# basic_tracker.net
KiCad netlist of a schematic drawn in EAGLE
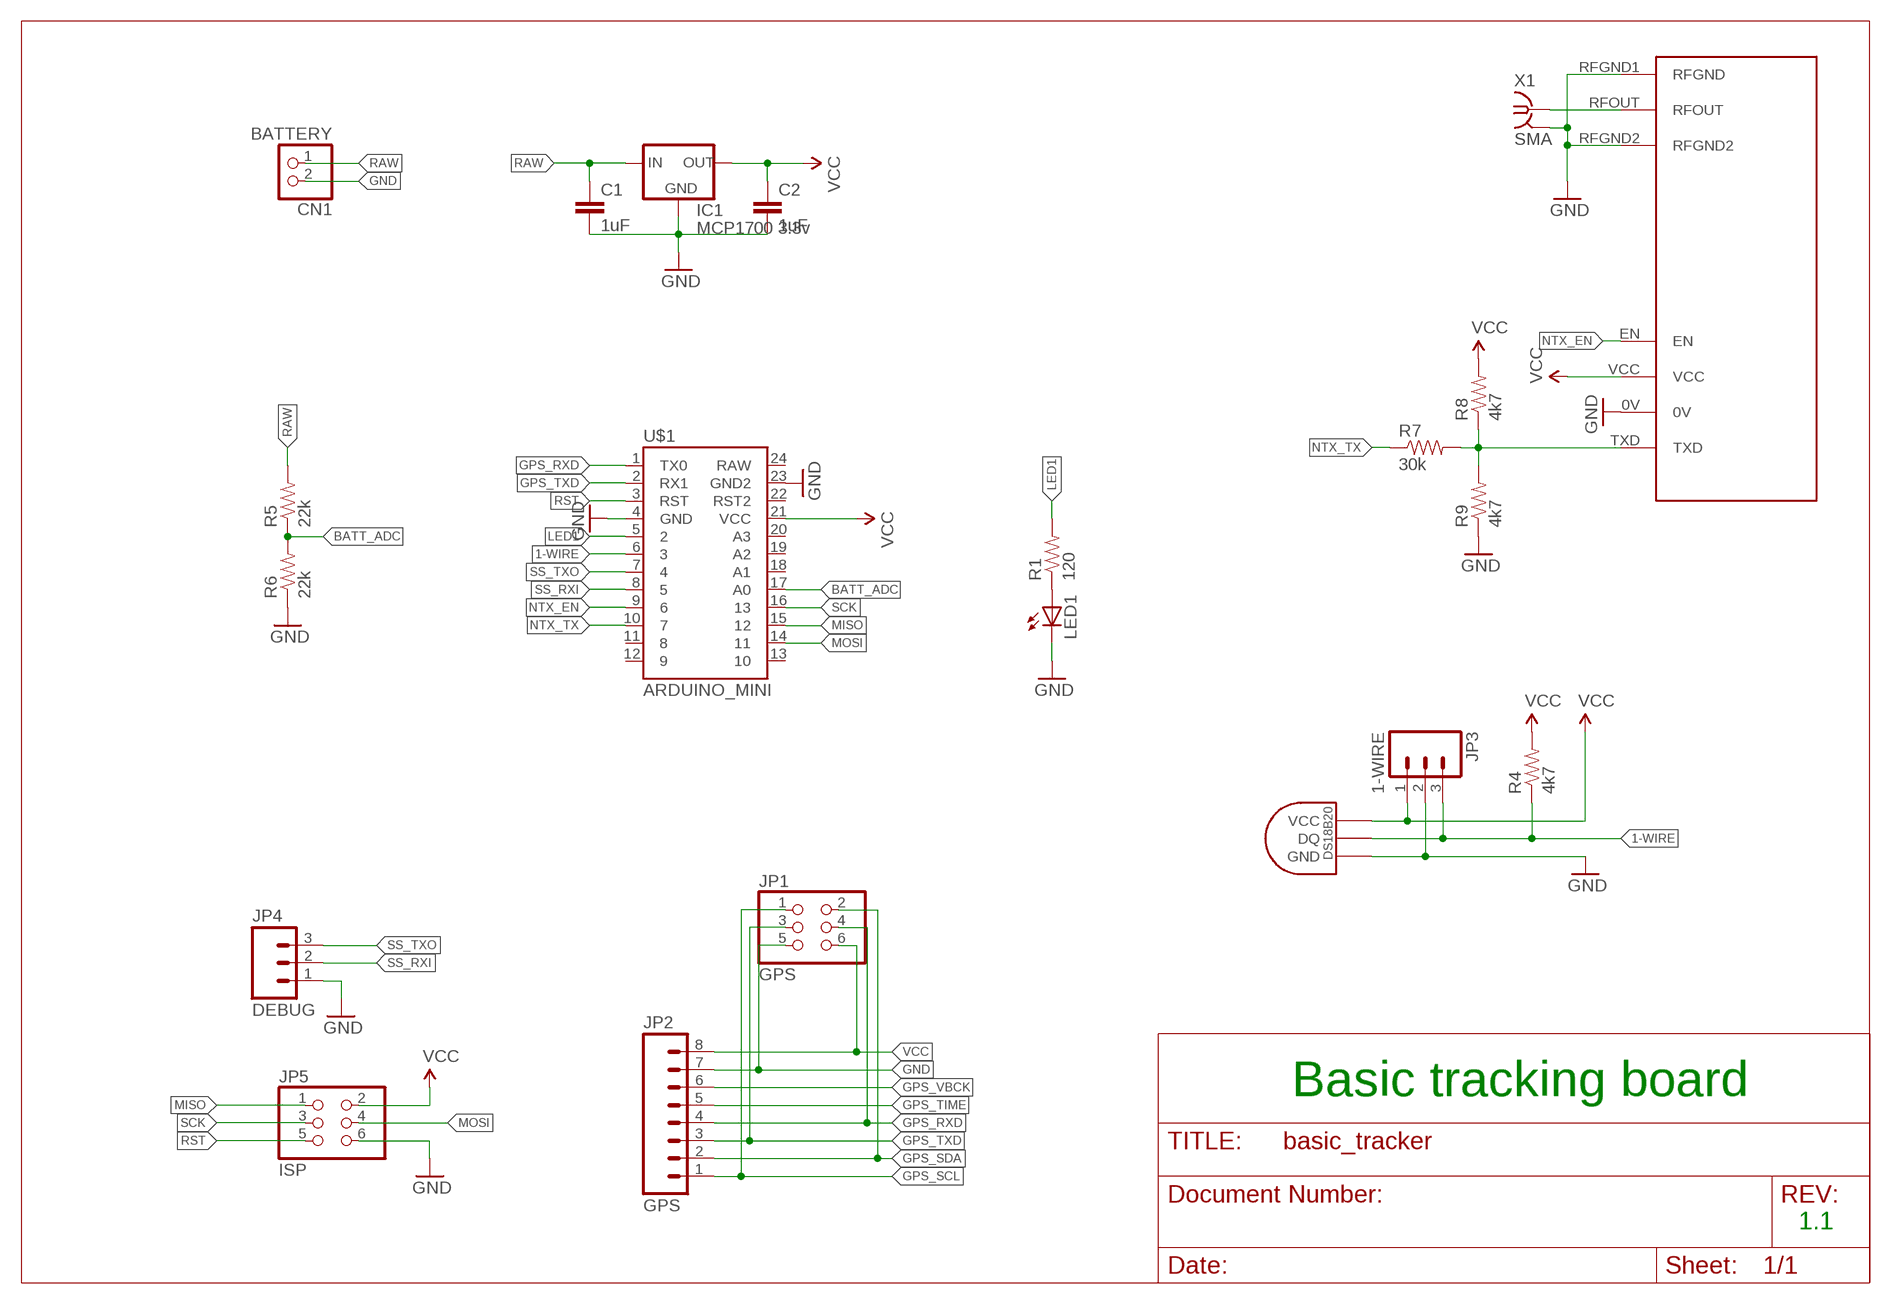
[diagram p0: schematic, sheet 1]

(export (version "E")
  (design (tool "Eeschema 10.0.6"))
  (components
    (comp (ref "C1")
      (value "1uF")
      (footprint "eagle-import:CAP-PTH-5MM")
      (libsource (lib "eagle-import") (part "CAPPTH1"))
    )
    (comp (ref "C2")
      (value "1uF")
      (footprint "eagle-import:CAP-PTH-5MM")
      (libsource (lib "eagle-import") (part "CAPPTH1"))
    )
    (comp (ref "CN1")
      (value "BATTERY")
      (footprint "eagle-import:JST-PH-2-THM-RA")
      (libsource (lib "eagle-import") (part "JST_2PIN-THM-RA"))
    )
    (comp (ref "IC1")
      (value "MCP1700 3.3v")
      (footprint "eagle-import:TO92-INLINE")
      (libsource (lib "eagle-import") (part "MCP1700INLINE"))
    )
    (comp (ref "JP1")
      (value "GPS")
      (footprint "eagle-import:2X03")
      (libsource (lib "eagle-import") (part "PINHD-2X3"))
    )
    (comp (ref "JP2")
      (value "GPS")
      (footprint "eagle-import:1X08")
      (libsource (lib "eagle-import") (part "M081X08"))
    )
    (comp (ref "JP3")
      (value "1-WIRE")
      (footprint "eagle-import:JST-3-PTH")
      (libsource (lib "eagle-import") (part "M03JST-PTH"))
    )
    (comp (ref "JP4")
      (value "DEBUG")
      (footprint "eagle-import:JST-3-PTH")
      (libsource (lib "eagle-import") (part "M03JST-PTH"))
    )
    (comp (ref "JP5")
      (value "ISP")
      (footprint "eagle-import:2X03")
      (libsource (lib "eagle-import") (part "PINHD-2X3"))
    )
    (comp (ref "LED1")
      (value "LED3MM")
      (footprint "eagle-import:LED3MM")
      (libsource (lib "eagle-import") (part "LED3MM"))
    )
    (comp (ref "R1")
      (value "120")
      (footprint "eagle-import:AXIAL-0.3")
      (libsource (lib "eagle-import") (part "RESISTORAXIAL-0.3"))
    )
    (comp (ref "R4")
      (value "4k7")
      (footprint "eagle-import:AXIAL-0.3")
      (libsource (lib "eagle-import") (part "RESISTORAXIAL-0.3"))
    )
    (comp (ref "R5")
      (value "22k")
      (footprint "eagle-import:AXIAL-0.3")
      (libsource (lib "eagle-import") (part "RESISTORAXIAL-0.3"))
    )
    (comp (ref "R6")
      (value "22k")
      (footprint "eagle-import:AXIAL-0.3")
      (libsource (lib "eagle-import") (part "RESISTORAXIAL-0.3"))
    )
    (comp (ref "R7")
      (value "30k")
      (footprint "eagle-import:AXIAL-0.3")
      (libsource (lib "eagle-import") (part "RESISTORAXIAL-0.3"))
    )
    (comp (ref "R8")
      (value "4k7")
      (footprint "eagle-import:AXIAL-0.3")
      (libsource (lib "eagle-import") (part "RESISTORAXIAL-0.3"))
    )
    (comp (ref "R9")
      (value "4k7")
      (footprint "eagle-import:AXIAL-0.3")
      (libsource (lib "eagle-import") (part "RESISTORAXIAL-0.3"))
    )
    (comp (ref "U$1")
      (value "ARDUINO_MINI")
      (footprint "eagle-import:ARDUINO_MINI")
      (libsource (lib "eagle-import") (part "ARDUINO_MINI"))
    )
    (comp (ref "U$2")
      (value "DS1820TO92")
      (footprint "eagle-import:DS1820")
      (libsource (lib "eagle-import") (part "DS1820TO92"))
    )
    (comp (ref "U$3")
      (value "NTX2-VERTICAL")
      (footprint "eagle-import:NTX2-VERTICAL")
      (libsource (lib "eagle-import") (part "NTX2-VERTICAL"))
    )
    (comp (ref "X1")
      (value "SMA")
      (footprint "eagle-import:BU-SMA-H")
      (libsource (lib "eagle-import") (part "BU-SMA-H"))
    )
  )
  (nets
    (net (code "1") (name "1-WIRE") (class "Default")
      (node (ref "JP3") (pin "3") (pinfunction "3_3") (pintype "passive"))
      (node (ref "R4") (pin "P$1") (pinfunction "1_P$1") (pintype "passive"))
      (node (ref "U$1") (pin "6") (pinfunction "3_6") (pintype "bidirectional"))
      (node (ref "U$2") (pin "DQ") (pinfunction "DQ_DQ") (pintype "bidirectional"))
    )
    (net (code "2") (name "BATT_ADC") (class "Default")
      (node (ref "R5") (pin "P$1") (pinfunction "1_P$1") (pintype "passive"))
      (node (ref "R6") (pin "P$2") (pinfunction "2_P$2") (pintype "passive"))
      (node (ref "U$1") (pin "17") (pinfunction "A0_17") (pintype "bidirectional"))
    )
    (net (code "3") (name "GND") (class "Default")
      (node (ref "C1") (pin "2") (pinfunction "2_2") (pintype "passive"))
      (node (ref "C2") (pin "2") (pinfunction "2_2") (pintype "passive"))
      (node (ref "CN1") (pin "2") (pinfunction "1_2") (pintype "passive"))
      (node (ref "IC1") (pin "1") (pinfunction "GND_1") (pintype "input"))
      (node (ref "JP1") (pin "5") (pinfunction "5_5") (pintype "passive"))
      (node (ref "JP2") (pin "7") (pinfunction "7_7") (pintype "passive"))
      (node (ref "JP3") (pin "2") (pinfunction "2_2") (pintype "passive"))
      (node (ref "JP4") (pin "1") (pinfunction "1_1") (pintype "passive"))
      (node (ref "JP5") (pin "6") (pinfunction "6_6") (pintype "passive"))
      (node (ref "LED1") (pin "K") (pinfunction "C_K") (pintype "passive"))
      (node (ref "R6") (pin "P$1") (pinfunction "1_P$1") (pintype "passive"))
      (node (ref "R9") (pin "P$1") (pinfunction "1_P$1") (pintype "passive"))
      (node (ref "U$1") (pin "23") (pinfunction "GND2_23") (pintype "bidirectional"))
      (node (ref "U$1") (pin "4") (pinfunction "GND_4") (pintype "bidirectional"))
      (node (ref "U$2") (pin "GND") (pinfunction "GND_GND") (pintype "power_in"))
      (node (ref "U$3") (pin "0V") (pinfunction "0V_0V") (pintype "bidirectional"))
      (node (ref "U$3") (pin "RFGND1") (pinfunction "RFGND_RFGND1") (pintype "bidirectional"))
      (node (ref "U$3") (pin "RFGND2") (pinfunction "RFGND2_RFGND2") (pintype "bidirectional"))
      (node (ref "X1") (pin "2") (pinfunction "GND_2") (pintype "power_in"))
    )
    (net (code "4") (name "GPS_RXD") (class "Default")
      (node (ref "JP1") (pin "4") (pinfunction "4_4") (pintype "passive"))
      (node (ref "JP2") (pin "4") (pinfunction "4_4") (pintype "passive"))
      (node (ref "U$1") (pin "1") (pinfunction "TX0_1") (pintype "bidirectional"))
    )
    (net (code "5") (name "GPS_SCL") (class "Default")
      (node (ref "JP1") (pin "1") (pinfunction "1_1") (pintype "passive"))
      (node (ref "JP2") (pin "1") (pinfunction "1_1") (pintype "passive"))
    )
    (net (code "6") (name "GPS_SDA") (class "Default")
      (node (ref "JP1") (pin "2") (pinfunction "2_2") (pintype "passive"))
      (node (ref "JP2") (pin "2") (pinfunction "2_2") (pintype "passive"))
    )
    (net (code "7") (name "GPS_TIME") (class "Default")
      (node (ref "JP2") (pin "5") (pinfunction "5_5") (pintype "passive"))
    )
    (net (code "8") (name "GPS_TXD") (class "Default")
      (node (ref "JP1") (pin "3") (pinfunction "3_3") (pintype "passive"))
      (node (ref "JP2") (pin "3") (pinfunction "3_3") (pintype "passive"))
      (node (ref "U$1") (pin "2") (pinfunction "RX1_2") (pintype "bidirectional"))
    )
    (net (code "9") (name "GPS_VBCK") (class "Default")
      (node (ref "JP2") (pin "6") (pinfunction "6_6") (pintype "passive"))
    )
    (net (code "10") (name "LED1") (class "Default")
      (node (ref "R1") (pin "P$2") (pinfunction "2_P$2") (pintype "passive"))
      (node (ref "U$1") (pin "5") (pinfunction "2_5") (pintype "bidirectional"))
    )
    (net (code "11") (name "MISO") (class "Default")
      (node (ref "JP5") (pin "1") (pinfunction "1_1") (pintype "passive"))
      (node (ref "U$1") (pin "15") (pinfunction "12_15") (pintype "bidirectional"))
    )
    (net (code "12") (name "MOSI") (class "Default")
      (node (ref "JP5") (pin "4") (pinfunction "4_4") (pintype "passive"))
      (node (ref "U$1") (pin "14") (pinfunction "11_14") (pintype "bidirectional"))
    )
    (net (code "13") (name "NTX_EN") (class "Default")
      (node (ref "U$1") (pin "9") (pinfunction "6_9") (pintype "bidirectional"))
      (node (ref "U$3") (pin "EN") (pinfunction "EN_EN") (pintype "bidirectional"))
    )
    (net (code "14") (name "NTX_TX") (class "Default")
      (node (ref "R7") (pin "P$1") (pinfunction "1_P$1") (pintype "passive"))
      (node (ref "U$1") (pin "10") (pinfunction "7_10") (pintype "bidirectional"))
    )
    (net (code "15") (name "Net-(R1-1)") (class "Default")
      (node (ref "LED1") (pin "A") (pinfunction "A_A") (pintype "passive"))
      (node (ref "R1") (pin "P$1") (pinfunction "1_P$1") (pintype "passive"))
    )
    (net (code "16") (name "Net-(R7-2)") (class "Default")
      (node (ref "R7") (pin "P$2") (pinfunction "2_P$2") (pintype "passive"))
      (node (ref "R8") (pin "P$1") (pinfunction "1_P$1") (pintype "passive"))
      (node (ref "R9") (pin "P$2") (pinfunction "2_P$2") (pintype "passive"))
      (node (ref "U$3") (pin "TXD") (pinfunction "TXD_TXD") (pintype "bidirectional"))
    )
    (net (code "17") (name "Net-(U$3-PadRFOUT)") (class "Default")
      (node (ref "U$3") (pin "RFOUT") (pinfunction "RFOUT_RFOUT") (pintype "bidirectional"))
      (node (ref "X1") (pin "1") (pinfunction "1_1") (pintype "passive"))
    )
    (net (code "18") (name "RAW") (class "Default")
      (node (ref "C1") (pin "1") (pinfunction "1_1") (pintype "passive"))
      (node (ref "CN1") (pin "1") (pinfunction "2_1") (pintype "passive"))
      (node (ref "IC1") (pin "2") (pinfunction "IN_2") (pintype "input"))
      (node (ref "R5") (pin "P$2") (pinfunction "2_P$2") (pintype "passive"))
    )
    (net (code "19") (name "RST") (class "Default")
      (node (ref "JP5") (pin "5") (pinfunction "5_5") (pintype "passive"))
      (node (ref "U$1") (pin "3") (pinfunction "RST_3") (pintype "bidirectional"))
    )
    (net (code "20") (name "SCK") (class "Default")
      (node (ref "JP5") (pin "3") (pinfunction "3_3") (pintype "passive"))
      (node (ref "U$1") (pin "16") (pinfunction "13_16") (pintype "bidirectional"))
    )
    (net (code "21") (name "SS_RXI") (class "Default")
      (node (ref "JP4") (pin "2") (pinfunction "2_2") (pintype "passive"))
      (node (ref "U$1") (pin "8") (pinfunction "5_8") (pintype "bidirectional"))
    )
    (net (code "22") (name "SS_TXO") (class "Default")
      (node (ref "JP4") (pin "3") (pinfunction "3_3") (pintype "passive"))
      (node (ref "U$1") (pin "7") (pinfunction "4_7") (pintype "bidirectional"))
    )
    (net (code "23") (name "VCC") (class "Default")
      (node (ref "C2") (pin "1") (pinfunction "1_1") (pintype "passive"))
      (node (ref "IC1") (pin "3") (pinfunction "OUT_3") (pintype "passive"))
      (node (ref "JP1") (pin "6") (pinfunction "6_6") (pintype "passive"))
      (node (ref "JP2") (pin "8") (pinfunction "8_8") (pintype "passive"))
      (node (ref "JP3") (pin "1") (pinfunction "1_1") (pintype "passive"))
      (node (ref "JP5") (pin "2") (pinfunction "2_2") (pintype "passive"))
      (node (ref "R4") (pin "P$2") (pinfunction "2_P$2") (pintype "passive"))
      (node (ref "R8") (pin "P$2") (pinfunction "2_P$2") (pintype "passive"))
      (node (ref "U$1") (pin "21") (pinfunction "VCC_21") (pintype "bidirectional"))
      (node (ref "U$2") (pin "VDD") (pinfunction "VCC_VDD") (pintype "power_in"))
      (node (ref "U$3") (pin "VCC") (pinfunction "VCC_VCC") (pintype "bidirectional"))
    )
    (net (code "24") (name "unconnected-(U$1-8-Pad11)") (class "Default")
      (node (ref "U$1") (pin "11") (pinfunction "8_11") (pintype "bidirectional"))
    )
    (net (code "25") (name "unconnected-(U$1-9-Pad12)") (class "Default")
      (node (ref "U$1") (pin "12") (pinfunction "9_12") (pintype "bidirectional"))
    )
    (net (code "26") (name "unconnected-(U$1-10-Pad13)") (class "Default")
      (node (ref "U$1") (pin "13") (pinfunction "10_13") (pintype "bidirectional"))
    )
    (net (code "27") (name "unconnected-(U$1-A1-Pad18)") (class "Default")
      (node (ref "U$1") (pin "18") (pinfunction "A1_18") (pintype "bidirectional"))
    )
    (net (code "28") (name "unconnected-(U$1-A2-Pad19)") (class "Default")
      (node (ref "U$1") (pin "19") (pinfunction "A2_19") (pintype "bidirectional"))
    )
    (net (code "29") (name "unconnected-(U$1-A3-Pad20)") (class "Default")
      (node (ref "U$1") (pin "20") (pinfunction "A3_20") (pintype "bidirectional"))
    )
    (net (code "30") (name "unconnected-(U$1-RAW-Pad24)") (class "Default")
      (node (ref "U$1") (pin "24") (pinfunction "RAW_24") (pintype "bidirectional"))
    )
    (net (code "31") (name "unconnected-(U$1-RST2-Pad22)") (class "Default")
      (node (ref "U$1") (pin "22") (pinfunction "RST2_22") (pintype "bidirectional"))
    )
  )
)
